# Adafruit_BMP388.net
KiCad netlist of a schematic drawn in EAGLE
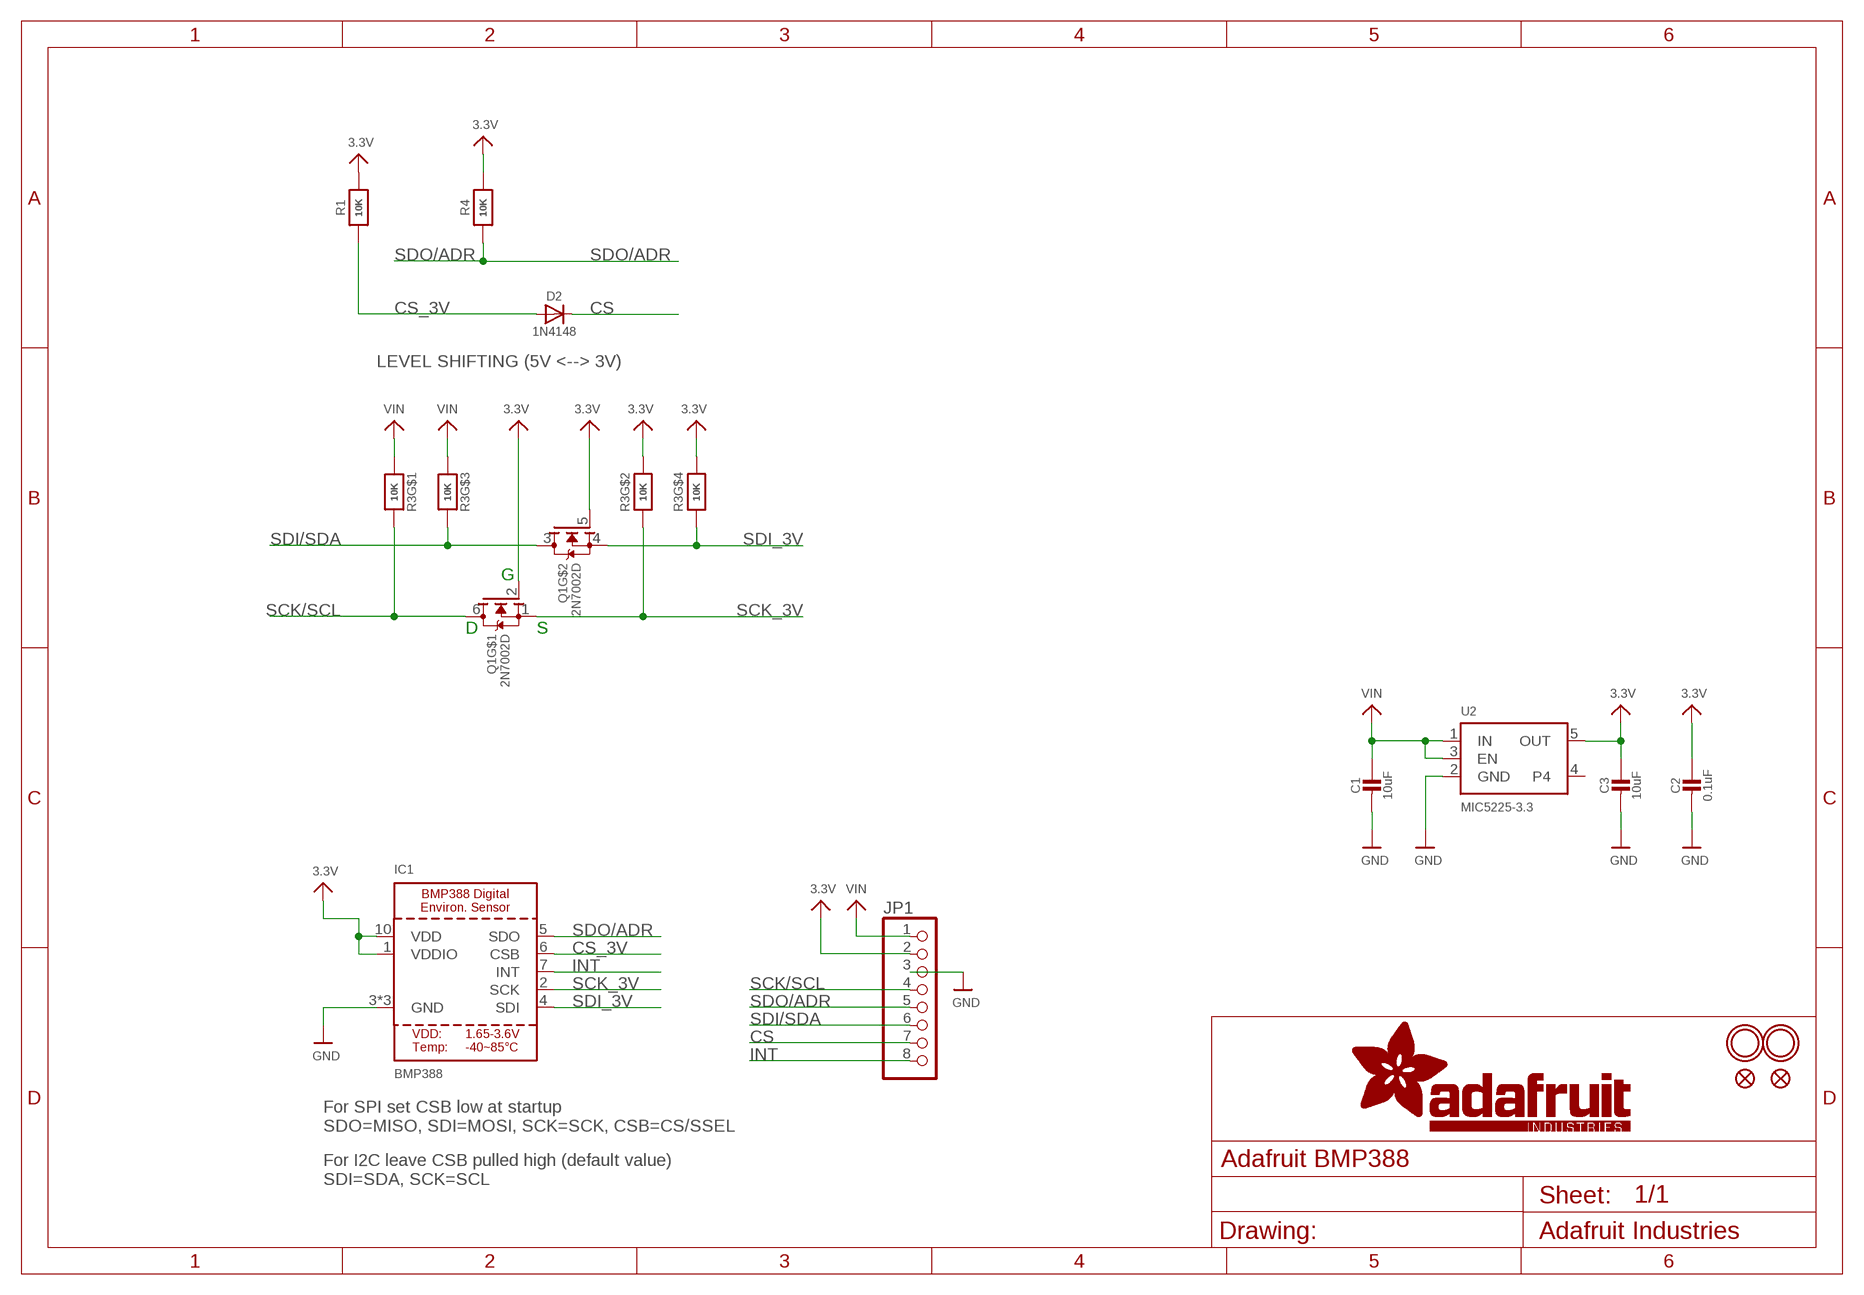
[diagram p0: schematic, sheet 1]

(export (version "E")
  (design (tool "Eeschema 10.0.6"))
  (components
    (comp (ref "C1")
      (value "10uF")
      (footprint "eagle-import:0805-NO")
      (libsource (lib "eagle-import") (part "CAP_CERAMIC0805-NOOUTLINE"))
    )
    (comp (ref "C2")
      (value "0.1uF")
      (footprint "eagle-import:0603-NO")
      (libsource (lib "eagle-import") (part "CAP_CERAMIC0603_NO"))
    )
    (comp (ref "C3")
      (value "10uF")
      (footprint "eagle-import:0805-NO")
      (libsource (lib "eagle-import") (part "CAP_CERAMIC0805-NOOUTLINE"))
    )
    (comp (ref "D2")
      (value "1N4148")
      (footprint "eagle-import:SOD-323")
      (libsource (lib "eagle-import") (part "DIODESOD-323"))
    )
    (comp (ref "IC1")
      (value "BMP388")
      (footprint "eagle-import:BMP388")
      (libsource (lib "eagle-import") (part "BMP388"))
    )
    (comp (ref "JP1")
      (value "HEADER-1X870MIL")
      (footprint "eagle-import:1X08_ROUND_70")
      (libsource (lib "eagle-import") (part "HEADER-1X870MIL"))
    )
    (comp (ref "Q1")
      (value "2N7002D")
      (footprint "eagle-import:SOT363")
      (libsource (lib "eagle-import") (part "MOSFET-N_DUAL"))
    )
    (comp (ref "R1")
      (value "10K")
      (footprint "eagle-import:0603-NO")
      (libsource (lib "eagle-import") (part "RESISTOR_0603_NOOUT"))
    )
    (comp (ref "R3")
      (value "10K")
      (footprint "eagle-import:RESPACK_4X0603")
      (libsource (lib "eagle-import") (part "RESISTOR_4PACK"))
    )
    (comp (ref "R4")
      (value "10K")
      (footprint "eagle-import:0603-NO")
      (libsource (lib "eagle-import") (part "RESISTOR_0603_NOOUT"))
    )
    (comp (ref "U$5")
      (value "FIDUCIAL_1MM")
      (footprint "eagle-import:FIDUCIAL_1MM")
      (libsource (lib "eagle-import") (part "FIDUCIAL_1MM"))
    )
    (comp (ref "U$7")
      (value "MOUNTINGHOLE2.0")
      (footprint "eagle-import:MOUNTINGHOLE_2.0_PLATED")
      (libsource (lib "eagle-import") (part "MOUNTINGHOLE2.0"))
    )
    (comp (ref "U$8")
      (value "MOUNTINGHOLE2.0")
      (footprint "eagle-import:MOUNTINGHOLE_2.0_PLATED")
      (libsource (lib "eagle-import") (part "MOUNTINGHOLE2.0"))
    )
    (comp (ref "U$15")
      (value "FIDUCIAL_1MM")
      (footprint "eagle-import:FIDUCIAL_1MM")
      (libsource (lib "eagle-import") (part "FIDUCIAL_1MM"))
    )
    (comp (ref "U2")
      (value "MIC5225-3.3")
      (footprint "eagle-import:SOT23-5")
      (libsource (lib "eagle-import") (part "VREG_SOT23-5"))
    )
  )
  (nets
    (net (code "1") (name "/CS") (class "Default")
      (node (ref "D2") (pin "C") (pinfunction "C_C") (pintype "passive"))
      (node (ref "JP1") (pin "7") (pinfunction "7_7") (pintype "passive"))
    )
    (net (code "2") (name "/CS_3V") (class "Default")
      (node (ref "D2") (pin "A") (pinfunction "A_A") (pintype "passive"))
      (node (ref "IC1") (pin "6") (pinfunction "CSB_6") (pintype "input"))
      (node (ref "R1") (pin "1") (pinfunction "1_1") (pintype "passive"))
    )
    (net (code "3") (name "/INT") (class "Default")
      (node (ref "IC1") (pin "7") (pinfunction "INT_7") (pintype "output"))
      (node (ref "JP1") (pin "8") (pinfunction "8_8") (pintype "passive"))
    )
    (net (code "4") (name "/SCK_3V") (class "Default")
      (node (ref "IC1") (pin "2") (pinfunction "SCK_2") (pintype "input"))
      (node (ref "Q1") (pin "1") (pinfunction "S_1") (pintype "bidirectional"))
      (node (ref "R3") (pin "7") (pinfunction "2_7") (pintype "passive"))
    )
    (net (code "5") (name "/SCK{slash}SCL") (class "Default")
      (node (ref "JP1") (pin "4") (pinfunction "4_4") (pintype "passive"))
      (node (ref "Q1") (pin "6") (pinfunction "D_6") (pintype "bidirectional"))
      (node (ref "R3") (pin "8") (pinfunction "2_8") (pintype "passive"))
    )
    (net (code "6") (name "/SDI_3V") (class "Default")
      (node (ref "IC1") (pin "4") (pinfunction "SDI_4") (pintype "input"))
      (node (ref "Q1") (pin "4") (pinfunction "S_4") (pintype "bidirectional"))
      (node (ref "R3") (pin "5") (pinfunction "2_5") (pintype "passive"))
    )
    (net (code "7") (name "/SDI{slash}SDA") (class "Default")
      (node (ref "JP1") (pin "6") (pinfunction "6_6") (pintype "passive"))
      (node (ref "Q1") (pin "3") (pinfunction "D_3") (pintype "bidirectional"))
      (node (ref "R3") (pin "6") (pinfunction "2_6") (pintype "passive"))
    )
    (net (code "8") (name "/SDO{slash}ADR") (class "Default")
      (node (ref "IC1") (pin "5") (pinfunction "SDO_5") (pintype "output"))
      (node (ref "JP1") (pin "5") (pinfunction "5_5") (pintype "passive"))
      (node (ref "R4") (pin "1") (pinfunction "1_1") (pintype "passive"))
    )
    (net (code "9") (name "3.3V") (class "Default")
      (node (ref "C2") (pin "1") (pinfunction "1_1") (pintype "passive"))
      (node (ref "C3") (pin "1") (pinfunction "1_1") (pintype "passive"))
      (node (ref "IC1") (pin "1") (pinfunction "VDDIO_1") (pintype "power_in"))
      (node (ref "IC1") (pin "10") (pinfunction "VDD_10") (pintype "power_in"))
      (node (ref "JP1") (pin "2") (pinfunction "2_2") (pintype "passive"))
      (node (ref "Q1") (pin "2") (pinfunction "G_2") (pintype "bidirectional"))
      (node (ref "Q1") (pin "5") (pinfunction "G_5") (pintype "bidirectional"))
      (node (ref "R1") (pin "2") (pinfunction "2_2") (pintype "passive"))
      (node (ref "R3") (pin "2") (pinfunction "1_2") (pintype "passive"))
      (node (ref "R3") (pin "4") (pinfunction "1_4") (pintype "passive"))
      (node (ref "R4") (pin "2") (pinfunction "2_2") (pintype "passive"))
      (node (ref "U2") (pin "5") (pinfunction "OUT_5") (pintype "power_in"))
    )
    (net (code "10") (name "GND") (class "Default")
      (node (ref "C1") (pin "2") (pinfunction "2_2") (pintype "passive"))
      (node (ref "C2") (pin "2") (pinfunction "2_2") (pintype "passive"))
      (node (ref "C3") (pin "2") (pinfunction "2_2") (pintype "passive"))
      (node (ref "IC1") (pin "3") (pinfunction "GND_3") (pintype "power_in"))
      (node (ref "IC1") (pin "8") (pinfunction "GND_8") (pintype "power_in"))
      (node (ref "IC1") (pin "9") (pinfunction "GND_9") (pintype "power_in"))
      (node (ref "JP1") (pin "3") (pinfunction "3_3") (pintype "passive"))
      (node (ref "U2") (pin "2") (pinfunction "GND_2") (pintype "power_in"))
    )
    (net (code "11") (name "VIN") (class "Default")
      (node (ref "C1") (pin "1") (pinfunction "1_1") (pintype "passive"))
      (node (ref "JP1") (pin "1") (pinfunction "1_1") (pintype "passive"))
      (node (ref "R3") (pin "1") (pinfunction "1_1") (pintype "passive"))
      (node (ref "R3") (pin "3") (pinfunction "1_3") (pintype "passive"))
      (node (ref "U2") (pin "1") (pinfunction "IN_1") (pintype "power_in"))
      (node (ref "U2") (pin "3") (pinfunction "EN_3") (pintype "input"))
    )
    (net (code "12") (name "unconnected-(U2-P4-Pad4)") (class "Default")
      (node (ref "U2") (pin "4") (pinfunction "P4_4") (pintype "bidirectional"))
    )
  )
)
